# hv3layerSW.net
KiCad netlist of a schematic drawn in EAGLE
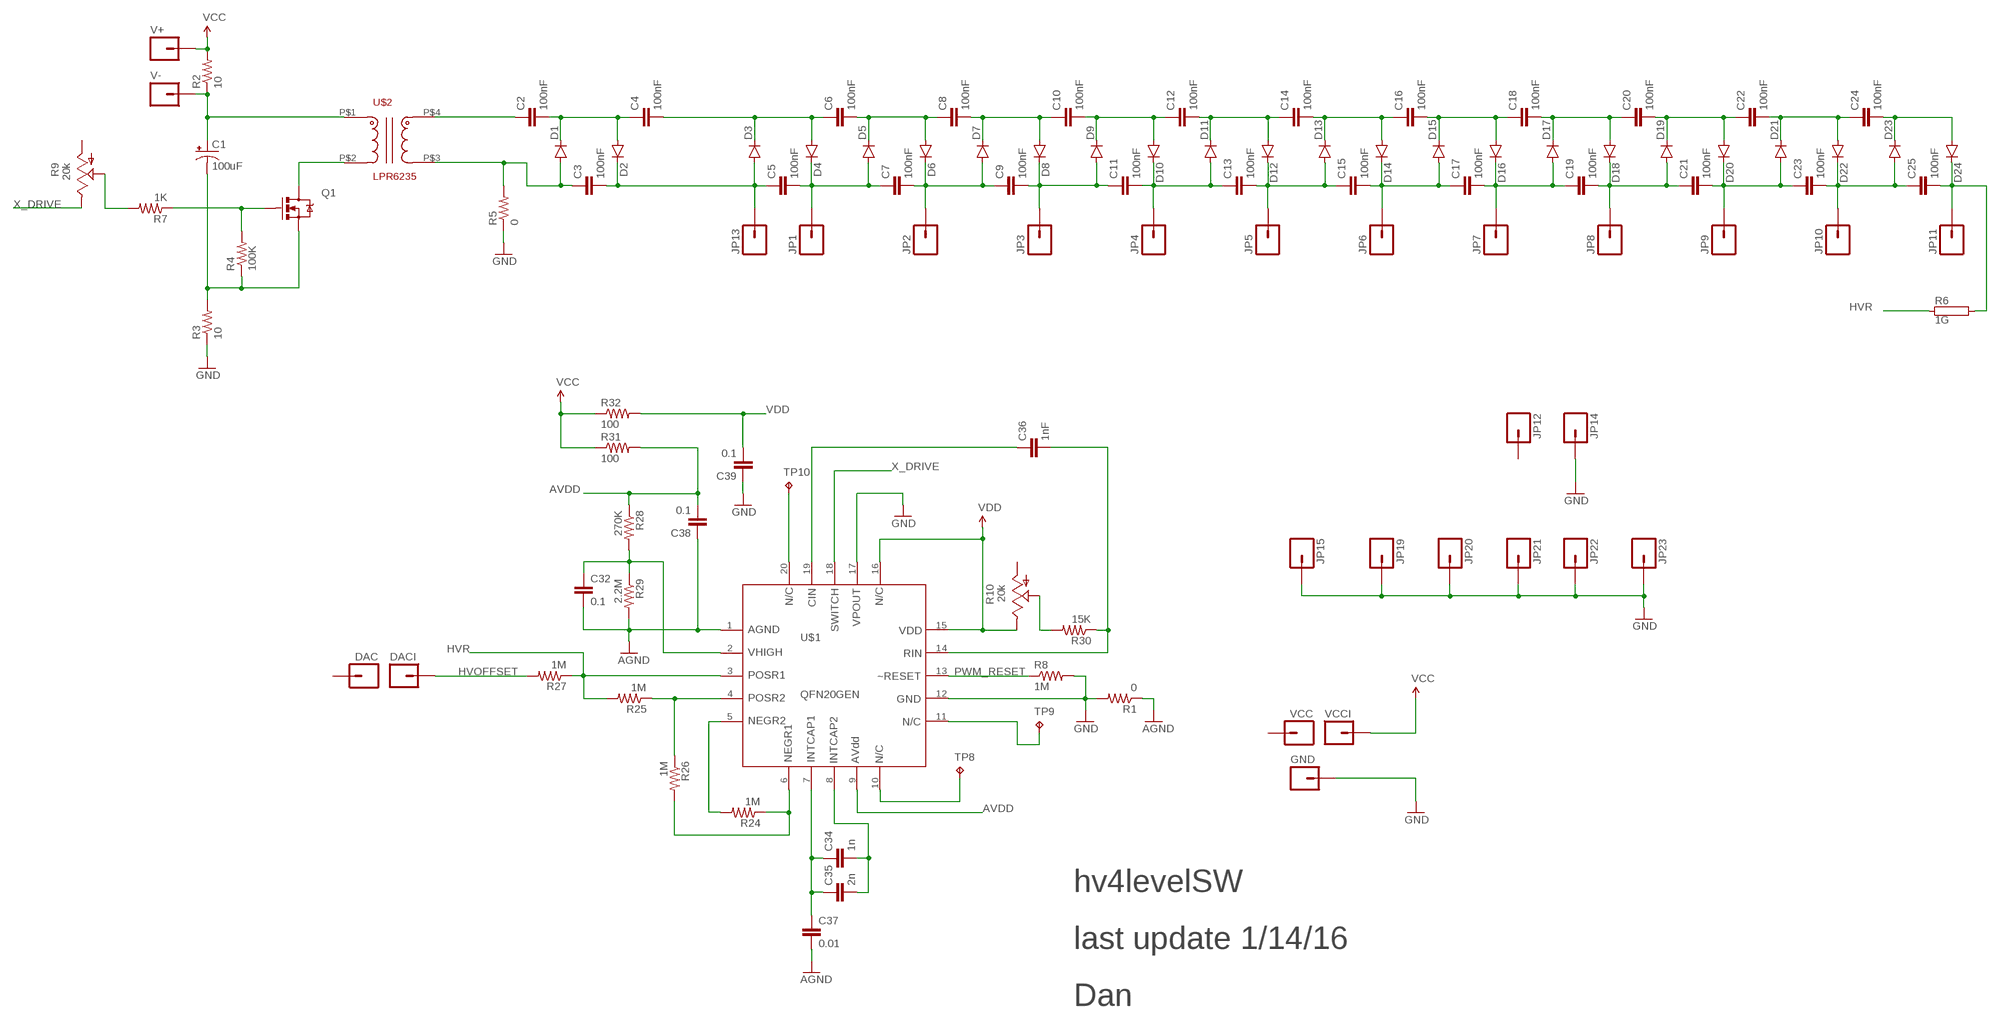
[diagram p0: schematic, sheet 1]

(export (version "E")
  (design (tool "Eeschema 10.0.6"))
  (components
    (comp (ref "C1")
      (value "100uF")
      (footprint "eagle-import:EIA6032")
      (libsource (lib "eagle-import") (part "CAP_POL6032"))
    )
    (comp (ref "C2")
      (value "100nF")
      (footprint "eagle-import:1210")
      (libsource (lib "eagle-import") (part "CAP1210"))
    )
    (comp (ref "C3")
      (value "100nF")
      (footprint "eagle-import:1210")
      (libsource (lib "eagle-import") (part "CAP1210"))
    )
    (comp (ref "C4")
      (value "100nF")
      (footprint "eagle-import:1210")
      (libsource (lib "eagle-import") (part "CAP1210"))
    )
    (comp (ref "C5")
      (value "100nF")
      (footprint "eagle-import:1210")
      (libsource (lib "eagle-import") (part "CAP1210"))
    )
    (comp (ref "C6")
      (value "100nF")
      (footprint "eagle-import:1210")
      (libsource (lib "eagle-import") (part "CAP1210"))
    )
    (comp (ref "C7")
      (value "100nF")
      (footprint "eagle-import:1210")
      (libsource (lib "eagle-import") (part "CAP1210"))
    )
    (comp (ref "C8")
      (value "100nF")
      (footprint "eagle-import:1210")
      (libsource (lib "eagle-import") (part "CAP1210"))
    )
    (comp (ref "C9")
      (value "100nF")
      (footprint "eagle-import:1210")
      (libsource (lib "eagle-import") (part "CAP1210"))
    )
    (comp (ref "C10")
      (value "100nF")
      (footprint "eagle-import:1210")
      (libsource (lib "eagle-import") (part "CAP1210"))
    )
    (comp (ref "C11")
      (value "100nF")
      (footprint "eagle-import:1210")
      (libsource (lib "eagle-import") (part "CAP1210"))
    )
    (comp (ref "C12")
      (value "100nF")
      (footprint "eagle-import:1210")
      (libsource (lib "eagle-import") (part "CAP1210"))
    )
    (comp (ref "C13")
      (value "100nF")
      (footprint "eagle-import:1210")
      (libsource (lib "eagle-import") (part "CAP1210"))
    )
    (comp (ref "C14")
      (value "100nF")
      (footprint "eagle-import:1210")
      (libsource (lib "eagle-import") (part "CAP1210"))
    )
    (comp (ref "C15")
      (value "100nF")
      (footprint "eagle-import:1210")
      (libsource (lib "eagle-import") (part "CAP1210"))
    )
    (comp (ref "C16")
      (value "100nF")
      (footprint "eagle-import:1210")
      (libsource (lib "eagle-import") (part "CAP1210"))
    )
    (comp (ref "C17")
      (value "100nF")
      (footprint "eagle-import:1210")
      (libsource (lib "eagle-import") (part "CAP1210"))
    )
    (comp (ref "C18")
      (value "100nF")
      (footprint "eagle-import:1210")
      (libsource (lib "eagle-import") (part "CAP1210"))
    )
    (comp (ref "C19")
      (value "100nF")
      (footprint "eagle-import:1210")
      (libsource (lib "eagle-import") (part "CAP1210"))
    )
    (comp (ref "C20")
      (value "100nF")
      (footprint "eagle-import:1210")
      (libsource (lib "eagle-import") (part "CAP1210"))
    )
    (comp (ref "C21")
      (value "100nF")
      (footprint "eagle-import:1210")
      (libsource (lib "eagle-import") (part "CAP1210"))
    )
    (comp (ref "C22")
      (value "100nF")
      (footprint "eagle-import:1210")
      (libsource (lib "eagle-import") (part "CAP1210"))
    )
    (comp (ref "C23")
      (value "100nF")
      (footprint "eagle-import:1210")
      (libsource (lib "eagle-import") (part "CAP1210"))
    )
    (comp (ref "C24")
      (value "100nF")
      (footprint "eagle-import:1210")
      (libsource (lib "eagle-import") (part "CAP1210"))
    )
    (comp (ref "C25")
      (value "100nF")
      (footprint "eagle-import:1210")
      (libsource (lib "eagle-import") (part "CAP1210"))
    )
    (comp (ref "C32")
      (value "0.1")
      (footprint "eagle-import:0805")
      (libsource (lib "eagle-import") (part "22UF-6.3V-20%(0805)"))
    )
    (comp (ref "C34")
      (value "1n")
      (footprint "eagle-import:0805")
      (libsource (lib "eagle-import") (part "22UF-6.3V-20%(0805)"))
    )
    (comp (ref "C35")
      (value "2n")
      (footprint "eagle-import:0805")
      (libsource (lib "eagle-import") (part "22UF-6.3V-20%(0805)"))
    )
    (comp (ref "C36")
      (value "1nF")
      (footprint "eagle-import:0805")
      (libsource (lib "eagle-import") (part "22UF-6.3V-20%(0805)"))
    )
    (comp (ref "C37")
      (value "0.01")
      (footprint "eagle-import:0805")
      (libsource (lib "eagle-import") (part "22UF-6.3V-20%(0805)"))
    )
    (comp (ref "C38")
      (value "0.1")
      (footprint "eagle-import:0805")
      (libsource (lib "eagle-import") (part "22UF-6.3V-20%(0805)"))
    )
    (comp (ref "C39")
      (value "0.1")
      (footprint "eagle-import:0805")
      (libsource (lib "eagle-import") (part "22UF-6.3V-20%(0805)"))
    )
    (comp (ref "D1")
      (value "DIODESOT23")
      (footprint "eagle-import:SOT23-3")
      (libsource (lib "eagle-import") (part "DIODESOT23"))
    )
    (comp (ref "D2")
      (value "DIODESOT23")
      (footprint "eagle-import:SOT23-3")
      (libsource (lib "eagle-import") (part "DIODESOT23"))
    )
    (comp (ref "D3")
      (value "DIODESOT23")
      (footprint "eagle-import:SOT23-3")
      (libsource (lib "eagle-import") (part "DIODESOT23"))
    )
    (comp (ref "D4")
      (value "DIODESOT23")
      (footprint "eagle-import:SOT23-3")
      (libsource (lib "eagle-import") (part "DIODESOT23"))
    )
    (comp (ref "D5")
      (value "DIODESOT23")
      (footprint "eagle-import:SOT23-3")
      (libsource (lib "eagle-import") (part "DIODESOT23"))
    )
    (comp (ref "D6")
      (value "DIODESOT23")
      (footprint "eagle-import:SOT23-3")
      (libsource (lib "eagle-import") (part "DIODESOT23"))
    )
    (comp (ref "D7")
      (value "DIODESOT23")
      (footprint "eagle-import:SOT23-3")
      (libsource (lib "eagle-import") (part "DIODESOT23"))
    )
    (comp (ref "D8")
      (value "DIODESOT23")
      (footprint "eagle-import:SOT23-3")
      (libsource (lib "eagle-import") (part "DIODESOT23"))
    )
    (comp (ref "D9")
      (value "DIODESOT23")
      (footprint "eagle-import:SOT23-3")
      (libsource (lib "eagle-import") (part "DIODESOT23"))
    )
    (comp (ref "D10")
      (value "DIODESOT23")
      (footprint "eagle-import:SOT23-3")
      (libsource (lib "eagle-import") (part "DIODESOT23"))
    )
    (comp (ref "D11")
      (value "DIODESOT23")
      (footprint "eagle-import:SOT23-3")
      (libsource (lib "eagle-import") (part "DIODESOT23"))
    )
    (comp (ref "D12")
      (value "DIODESOT23")
      (footprint "eagle-import:SOT23-3")
      (libsource (lib "eagle-import") (part "DIODESOT23"))
    )
    (comp (ref "D13")
      (value "DIODESOT23")
      (footprint "eagle-import:SOT23-3")
      (libsource (lib "eagle-import") (part "DIODESOT23"))
    )
    (comp (ref "D14")
      (value "DIODESOT23")
      (footprint "eagle-import:SOT23-3")
      (libsource (lib "eagle-import") (part "DIODESOT23"))
    )
    (comp (ref "D15")
      (value "DIODESOT23")
      (footprint "eagle-import:SOT23-3")
      (libsource (lib "eagle-import") (part "DIODESOT23"))
    )
    (comp (ref "D16")
      (value "DIODESOT23")
      (footprint "eagle-import:SOT23-3")
      (libsource (lib "eagle-import") (part "DIODESOT23"))
    )
    (comp (ref "D17")
      (value "DIODESOT23")
      (footprint "eagle-import:SOT23-3")
      (libsource (lib "eagle-import") (part "DIODESOT23"))
    )
    (comp (ref "D18")
      (value "DIODESOT23")
      (footprint "eagle-import:SOT23-3")
      (libsource (lib "eagle-import") (part "DIODESOT23"))
    )
    (comp (ref "D19")
      (value "DIODESOT23")
      (footprint "eagle-import:SOT23-3")
      (libsource (lib "eagle-import") (part "DIODESOT23"))
    )
    (comp (ref "D20")
      (value "DIODESOT23")
      (footprint "eagle-import:SOT23-3")
      (libsource (lib "eagle-import") (part "DIODESOT23"))
    )
    (comp (ref "D21")
      (value "DIODESOT23")
      (footprint "eagle-import:SOT23-3")
      (libsource (lib "eagle-import") (part "DIODESOT23"))
    )
    (comp (ref "D22")
      (value "DIODESOT23")
      (footprint "eagle-import:SOT23-3")
      (libsource (lib "eagle-import") (part "DIODESOT23"))
    )
    (comp (ref "D23")
      (value "DIODESOT23")
      (footprint "eagle-import:SOT23-3")
      (libsource (lib "eagle-import") (part "DIODESOT23"))
    )
    (comp (ref "D24")
      (value "DIODESOT23")
      (footprint "eagle-import:SOT23-3")
      (libsource (lib "eagle-import") (part "DIODESOT23"))
    )
    (comp (ref "DAC")
      (value "M01PTH")
      (footprint "eagle-import:1X01")
      (libsource (lib "eagle-import") (part "M01PTH"))
    )
    (comp (ref "DACI")
      (value "M01PTH")
      (footprint "eagle-import:1X01")
      (libsource (lib "eagle-import") (part "M01PTH"))
    )
    (comp (ref "GND")
      (value "M01PTH")
      (footprint "eagle-import:1X01")
      (libsource (lib "eagle-import") (part "M01PTH"))
    )
    (comp (ref "JP1")
      (value "M01PTH")
      (footprint "eagle-import:1X01")
      (libsource (lib "eagle-import") (part "M01PTH"))
    )
    (comp (ref "JP2")
      (value "M01PTH")
      (footprint "eagle-import:1X01")
      (libsource (lib "eagle-import") (part "M01PTH"))
    )
    (comp (ref "JP3")
      (value "M01PTH")
      (footprint "eagle-import:1X01")
      (libsource (lib "eagle-import") (part "M01PTH"))
    )
    (comp (ref "JP4")
      (value "M01PTH")
      (footprint "eagle-import:1X01")
      (libsource (lib "eagle-import") (part "M01PTH"))
    )
    (comp (ref "JP5")
      (value "M01PTH")
      (footprint "eagle-import:1X01")
      (libsource (lib "eagle-import") (part "M01PTH"))
    )
    (comp (ref "JP6")
      (value "M01PTH")
      (footprint "eagle-import:1X01")
      (libsource (lib "eagle-import") (part "M01PTH"))
    )
    (comp (ref "JP7")
      (value "M01PTH")
      (footprint "eagle-import:1X01")
      (libsource (lib "eagle-import") (part "M01PTH"))
    )
    (comp (ref "JP8")
      (value "M01PTH")
      (footprint "eagle-import:1X01")
      (libsource (lib "eagle-import") (part "M01PTH"))
    )
    (comp (ref "JP9")
      (value "M01PTH")
      (footprint "eagle-import:1X01")
      (libsource (lib "eagle-import") (part "M01PTH"))
    )
    (comp (ref "JP10")
      (value "M01PTH")
      (footprint "eagle-import:1X01")
      (libsource (lib "eagle-import") (part "M01PTH"))
    )
    (comp (ref "JP11")
      (value "M01PTH")
      (footprint "eagle-import:1X01")
      (libsource (lib "eagle-import") (part "M01PTH"))
    )
    (comp (ref "JP12")
      (value "M01PTH")
      (footprint "eagle-import:1X01")
      (libsource (lib "eagle-import") (part "M01PTH"))
    )
    (comp (ref "JP13")
      (value "M01PTH")
      (footprint "eagle-import:1X01")
      (libsource (lib "eagle-import") (part "M01PTH"))
    )
    (comp (ref "JP14")
      (value "M01PTH")
      (footprint "eagle-import:1X01")
      (libsource (lib "eagle-import") (part "M01PTH"))
    )
    (comp (ref "JP15")
      (value "M01PTH")
      (footprint "eagle-import:1X01")
      (libsource (lib "eagle-import") (part "M01PTH"))
    )
    (comp (ref "JP19")
      (value "M01PTH")
      (footprint "eagle-import:1X01")
      (libsource (lib "eagle-import") (part "M01PTH"))
    )
    (comp (ref "JP20")
      (value "M01PTH")
      (footprint "eagle-import:1X01")
      (libsource (lib "eagle-import") (part "M01PTH"))
    )
    (comp (ref "JP21")
      (value "M01PTH")
      (footprint "eagle-import:1X01")
      (libsource (lib "eagle-import") (part "M01PTH"))
    )
    (comp (ref "JP22")
      (value "M01PTH")
      (footprint "eagle-import:1X01")
      (libsource (lib "eagle-import") (part "M01PTH"))
    )
    (comp (ref "JP23")
      (value "M01PTH")
      (footprint "eagle-import:1X01")
      (libsource (lib "eagle-import") (part "M01PTH"))
    )
    (comp (ref "Q1")
      (value "MOSFET-NCHANNELAO3404A")
      (footprint "eagle-import:SOT23-3")
      (libsource (lib "eagle-import") (part "MOSFET-NCHANNELAO3404A"))
    )
    (comp (ref "R1")
      (value "0")
      (footprint "eagle-import:0805")
      (libsource (lib "eagle-import") (part "RESISTOR0805-RES"))
    )
    (comp (ref "R2")
      (value "10")
      (footprint "eagle-import:R2512")
      (libsource (lib "eagle-import") (part "SparkFun-Resistors_RESISTOR2512"))
    )
    (comp (ref "R3")
      (value "10")
      (footprint "eagle-import:R2512")
      (libsource (lib "eagle-import") (part "SparkFun-Resistors_RESISTOR2512"))
    )
    (comp (ref "R4")
      (value "100K")
      (footprint "eagle-import:0805")
      (libsource (lib "eagle-import") (part "RESISTOR0805-RES"))
    )
    (comp (ref "R5")
      (value "0")
      (footprint "eagle-import:0805")
      (libsource (lib "eagle-import") (part "RESISTOR0805-RES"))
    )
    (comp (ref "R6")
      (value "1G")
      (footprint "eagle-import:CA4090")
      (libsource (lib "eagle-import") (part "RCA4090"))
    )
    (comp (ref "R7")
      (value "1K")
      (footprint "eagle-import:0805")
      (libsource (lib "eagle-import") (part "RESISTOR0805-RES"))
    )
    (comp (ref "R8")
      (value "1M")
      (footprint "eagle-import:0805")
      (libsource (lib "eagle-import") (part "RESISTOR0805-RES"))
    )
    (comp (ref "R9")
      (value "20k")
      (footprint "eagle-import:3223J")
      (libsource (lib "eagle-import") (part "TRIM_US-3223J"))
    )
    (comp (ref "R10")
      (value "20k")
      (footprint "eagle-import:3223J")
      (libsource (lib "eagle-import") (part "TRIM_US-3223J"))
    )
    (comp (ref "R24")
      (value "1M")
      (footprint "eagle-import:0805")
      (libsource (lib "eagle-import") (part "RESISTOR0805-RES"))
    )
    (comp (ref "R25")
      (value "1M")
      (footprint "eagle-import:0805")
      (libsource (lib "eagle-import") (part "RESISTOR0805-RES"))
    )
    (comp (ref "R26")
      (value "1M")
      (footprint "eagle-import:0805")
      (libsource (lib "eagle-import") (part "RESISTOR0805-RES"))
    )
    (comp (ref "R27")
      (value "1M")
      (footprint "eagle-import:0805")
      (libsource (lib "eagle-import") (part "RESISTOR0805-RES"))
    )
    (comp (ref "R28")
      (value "270K")
      (footprint "eagle-import:0805")
      (libsource (lib "eagle-import") (part "RESISTOR0805-RES"))
    )
    (comp (ref "R29")
      (value "2.2M")
      (footprint "eagle-import:0805")
      (libsource (lib "eagle-import") (part "RESISTOR0805-RES"))
    )
    (comp (ref "R30")
      (value "15K")
      (footprint "eagle-import:0805")
      (libsource (lib "eagle-import") (part "RESISTOR0805-RES"))
    )
    (comp (ref "R31")
      (value "100")
      (footprint "eagle-import:0805")
      (libsource (lib "eagle-import") (part "RESISTOR0805-RES"))
    )
    (comp (ref "R32")
      (value "100")
      (footprint "eagle-import:0805")
      (libsource (lib "eagle-import") (part "RESISTOR0805-RES"))
    )
    (comp (ref "TP8")
      (value "TPTP10R")
      (footprint "eagle-import:TP10R")
      (libsource (lib "eagle-import") (part "TPTP10R"))
    )
    (comp (ref "TP9")
      (value "TPTP10R")
      (footprint "eagle-import:TP10R")
      (libsource (lib "eagle-import") (part "TPTP10R"))
    )
    (comp (ref "TP10")
      (value "TPTP10R")
      (footprint "eagle-import:TP10R")
      (libsource (lib "eagle-import") (part "TPTP10R"))
    )
    (comp (ref "U$1")
      (value "QFN20GEN")
      (footprint "eagle-import:QFN20")
      (libsource (lib "eagle-import") (part "QFN20GEN"))
    )
    (comp (ref "U$2")
      (value "LPR6235")
      (footprint "eagle-import:LPR6235")
      (libsource (lib "eagle-import") (part "LPR6235"))
    )
    (comp (ref "V+")
      (value "M01PTH")
      (footprint "eagle-import:1X01")
      (libsource (lib "eagle-import") (part "M01PTH"))
    )
    (comp (ref "V-")
      (value "M01PTH")
      (footprint "eagle-import:1X01")
      (libsource (lib "eagle-import") (part "M01PTH"))
    )
    (comp (ref "VCC")
      (value "M01PTH")
      (footprint "eagle-import:1X01")
      (libsource (lib "eagle-import") (part "M01PTH"))
    )
    (comp (ref "VCCI")
      (value "M01PTH")
      (footprint "eagle-import:1X01")
      (libsource (lib "eagle-import") (part "M01PTH"))
    )
  )
  (nets
    (net (code "1") (name "/AVDD") (class "Default")
      (node (ref "C38") (pin "2") (pinfunction "2_2") (pintype "passive"))
      (node (ref "R28") (pin "1") (pinfunction "1_1") (pintype "passive"))
      (node (ref "R31") (pin "2") (pinfunction "2_2") (pintype "passive"))
      (node (ref "U$1") (pin "9") (pinfunction "P$9_9") (pintype "bidirectional"))
    )
    (net (code "2") (name "/HVOFFSET") (class "Default")
      (node (ref "DACI") (pin "1") (pinfunction "1_1") (pintype "passive"))
      (node (ref "R27") (pin "2") (pinfunction "2_2") (pintype "passive"))
    )
    (net (code "3") (name "/HVR") (class "Default")
      (node (ref "R25") (pin "2") (pinfunction "2_2") (pintype "passive"))
      (node (ref "R27") (pin "1") (pinfunction "1_1") (pintype "passive"))
      (node (ref "R6") (pin "1") (pinfunction "1_1") (pintype "passive"))
      (node (ref "U$1") (pin "3") (pinfunction "P$3_3") (pintype "bidirectional"))
    )
    (net (code "4") (name "/PWM_RESET") (class "Default")
      (node (ref "R8") (pin "1") (pinfunction "1_1") (pintype "passive"))
      (node (ref "U$1") (pin "13") (pinfunction "P$13_13") (pintype "bidirectional"))
    )
    (net (code "5") (name "/X_DRIVE") (class "Default")
      (node (ref "R9") (pin "3") (pinfunction "E_3") (pintype "passive"))
      (node (ref "U$1") (pin "18") (pinfunction "P$18_18") (pintype "bidirectional"))
    )
    (net (code "6") (name "AGND") (class "Default")
      (node (ref "C32") (pin "2") (pinfunction "2_2") (pintype "passive"))
      (node (ref "C37") (pin "2") (pinfunction "2_2") (pintype "passive"))
      (node (ref "C38") (pin "1") (pinfunction "1_1") (pintype "passive"))
      (node (ref "R1") (pin "1") (pinfunction "1_1") (pintype "passive"))
      (node (ref "R29") (pin "2") (pinfunction "2_2") (pintype "passive"))
      (node (ref "U$1") (pin "1") (pinfunction "P$1_1") (pintype "bidirectional"))
    )
    (net (code "7") (name "GND") (class "Default")
      (node (ref "C39") (pin "1") (pinfunction "1_1") (pintype "passive"))
      (node (ref "GND") (pin "1") (pinfunction "1_1") (pintype "passive"))
      (node (ref "JP14") (pin "1") (pinfunction "1_1") (pintype "passive"))
      (node (ref "JP15") (pin "1") (pinfunction "1_1") (pintype "passive"))
      (node (ref "JP19") (pin "1") (pinfunction "1_1") (pintype "passive"))
      (node (ref "JP20") (pin "1") (pinfunction "1_1") (pintype "passive"))
      (node (ref "JP21") (pin "1") (pinfunction "1_1") (pintype "passive"))
      (node (ref "JP22") (pin "1") (pinfunction "1_1") (pintype "passive"))
      (node (ref "JP23") (pin "1") (pinfunction "1_1") (pintype "passive"))
      (node (ref "R1") (pin "2") (pinfunction "2_2") (pintype "passive"))
      (node (ref "R3") (pin "1") (pinfunction "1_1") (pintype "passive"))
      (node (ref "R5") (pin "1") (pinfunction "1_1") (pintype "passive"))
      (node (ref "R8") (pin "2") (pinfunction "2_2") (pintype "passive"))
      (node (ref "U$1") (pin "12") (pinfunction "P$12_12") (pintype "bidirectional"))
      (node (ref "U$1") (pin "17") (pinfunction "P$17_17") (pintype "bidirectional"))
    )
    (net (code "8") (name "Net-(C1-+)") (class "Default")
      (node (ref "C1") (pin "P$1") (pinfunction "+_P$1") (pintype "passive"))
      (node (ref "R2") (pin "1") (pinfunction "1_1") (pintype "passive"))
      (node (ref "U$2") (pin "P$1") (pinfunction "1_P$1") (pintype "passive"))
      (node (ref "V-") (pin "1") (pinfunction "1_1") (pintype "passive"))
    )
    (net (code "9") (name "Net-(C1--)") (class "Default")
      (node (ref "C1") (pin "P$2") (pinfunction "-_P$2") (pintype "passive"))
      (node (ref "Q1") (pin "2") (pinfunction "S_2") (pintype "passive"))
      (node (ref "R3") (pin "2") (pinfunction "2_2") (pintype "passive"))
      (node (ref "R4") (pin "1") (pinfunction "1_1") (pintype "passive"))
    )
    (net (code "10") (name "Net-(D1-A)") (class "Default")
      (node (ref "C3") (pin "1") (pinfunction "1_1") (pintype "passive"))
      (node (ref "D1") (pin "1") (pinfunction "A_1") (pintype "passive"))
      (node (ref "R5") (pin "2") (pinfunction "2_2") (pintype "passive"))
      (node (ref "U$2") (pin "P$3") (pinfunction "5_P$3") (pintype "passive"))
    )
    (net (code "11") (name "Net-(D1-C)") (class "Default")
      (node (ref "C2") (pin "2") (pinfunction "2_2") (pintype "passive"))
      (node (ref "C4") (pin "1") (pinfunction "1_1") (pintype "passive"))
      (node (ref "D1") (pin "3") (pinfunction "C_3") (pintype "passive"))
      (node (ref "D2") (pin "1") (pinfunction "A_1") (pintype "passive"))
    )
    (net (code "12") (name "Net-(D2-C)") (class "Default")
      (node (ref "C3") (pin "2") (pinfunction "2_2") (pintype "passive"))
      (node (ref "C5") (pin "1") (pinfunction "1_1") (pintype "passive"))
      (node (ref "D2") (pin "3") (pinfunction "C_3") (pintype "passive"))
      (node (ref "D3") (pin "1") (pinfunction "A_1") (pintype "passive"))
      (node (ref "JP13") (pin "1") (pinfunction "1_1") (pintype "passive"))
    )
    (net (code "13") (name "Net-(D3-C)") (class "Default")
      (node (ref "C4") (pin "2") (pinfunction "2_2") (pintype "passive"))
      (node (ref "C6") (pin "1") (pinfunction "1_1") (pintype "passive"))
      (node (ref "D3") (pin "3") (pinfunction "C_3") (pintype "passive"))
      (node (ref "D4") (pin "1") (pinfunction "A_1") (pintype "passive"))
    )
    (net (code "14") (name "Net-(D4-C)") (class "Default")
      (node (ref "C5") (pin "2") (pinfunction "2_2") (pintype "passive"))
      (node (ref "C7") (pin "1") (pinfunction "1_1") (pintype "passive"))
      (node (ref "D4") (pin "3") (pinfunction "C_3") (pintype "passive"))
      (node (ref "D5") (pin "1") (pinfunction "A_1") (pintype "passive"))
      (node (ref "JP1") (pin "1") (pinfunction "1_1") (pintype "passive"))
    )
    (net (code "15") (name "Net-(D5-C)") (class "Default")
      (node (ref "C6") (pin "2") (pinfunction "2_2") (pintype "passive"))
      (node (ref "C8") (pin "1") (pinfunction "1_1") (pintype "passive"))
      (node (ref "D5") (pin "3") (pinfunction "C_3") (pintype "passive"))
      (node (ref "D6") (pin "1") (pinfunction "A_1") (pintype "passive"))
    )
    (net (code "16") (name "Net-(D6-C)") (class "Default")
      (node (ref "C7") (pin "2") (pinfunction "2_2") (pintype "passive"))
      (node (ref "C9") (pin "1") (pinfunction "1_1") (pintype "passive"))
      (node (ref "D6") (pin "3") (pinfunction "C_3") (pintype "passive"))
      (node (ref "D7") (pin "1") (pinfunction "A_1") (pintype "passive"))
      (node (ref "JP2") (pin "1") (pinfunction "1_1") (pintype "passive"))
    )
    (net (code "17") (name "Net-(D7-C)") (class "Default")
      (node (ref "C10") (pin "1") (pinfunction "1_1") (pintype "passive"))
      (node (ref "C8") (pin "2") (pinfunction "2_2") (pintype "passive"))
      (node (ref "D7") (pin "3") (pinfunction "C_3") (pintype "passive"))
      (node (ref "D8") (pin "1") (pinfunction "A_1") (pintype "passive"))
    )
    (net (code "18") (name "Net-(D8-C)") (class "Default")
      (node (ref "C11") (pin "1") (pinfunction "1_1") (pintype "passive"))
      (node (ref "C9") (pin "2") (pinfunction "2_2") (pintype "passive"))
      (node (ref "D8") (pin "3") (pinfunction "C_3") (pintype "passive"))
      (node (ref "D9") (pin "1") (pinfunction "A_1") (pintype "passive"))
      (node (ref "JP3") (pin "1") (pinfunction "1_1") (pintype "passive"))
    )
    (net (code "19") (name "Net-(D10-A)") (class "Default")
      (node (ref "C10") (pin "2") (pinfunction "2_2") (pintype "passive"))
      (node (ref "C12") (pin "1") (pinfunction "1_1") (pintype "passive"))
      (node (ref "D10") (pin "1") (pinfunction "A_1") (pintype "passive"))
      (node (ref "D9") (pin "3") (pinfunction "C_3") (pintype "passive"))
    )
    (net (code "20") (name "Net-(D10-C)") (class "Default")
      (node (ref "C11") (pin "2") (pinfunction "2_2") (pintype "passive"))
      (node (ref "C13") (pin "1") (pinfunction "1_1") (pintype "passive"))
      (node (ref "D10") (pin "3") (pinfunction "C_3") (pintype "passive"))
      (node (ref "D11") (pin "1") (pinfunction "A_1") (pintype "passive"))
      (node (ref "JP4") (pin "1") (pinfunction "1_1") (pintype "passive"))
    )
    (net (code "21") (name "Net-(D11-C)") (class "Default")
      (node (ref "C12") (pin "2") (pinfunction "2_2") (pintype "passive"))
      (node (ref "C14") (pin "1") (pinfunction "1_1") (pintype "passive"))
      (node (ref "D11") (pin "3") (pinfunction "C_3") (pintype "passive"))
      (node (ref "D12") (pin "1") (pinfunction "A_1") (pintype "passive"))
    )
    (net (code "22") (name "Net-(D12-C)") (class "Default")
      (node (ref "C13") (pin "2") (pinfunction "2_2") (pintype "passive"))
      (node (ref "C15") (pin "1") (pinfunction "1_1") (pintype "passive"))
      (node (ref "D12") (pin "3") (pinfunction "C_3") (pintype "passive"))
      (node (ref "D13") (pin "1") (pinfunction "A_1") (pintype "passive"))
      (node (ref "JP5") (pin "1") (pinfunction "1_1") (pintype "passive"))
    )
    (net (code "23") (name "Net-(D13-C)") (class "Default")
      (node (ref "C14") (pin "2") (pinfunction "2_2") (pintype "passive"))
      (node (ref "C16") (pin "1") (pinfunction "1_1") (pintype "passive"))
      (node (ref "D13") (pin "3") (pinfunction "C_3") (pintype "passive"))
      (node (ref "D14") (pin "1") (pinfunction "A_1") (pintype "passive"))
    )
    (net (code "24") (name "Net-(D14-C)") (class "Default")
      (node (ref "C15") (pin "2") (pinfunction "2_2") (pintype "passive"))
      (node (ref "C17") (pin "1") (pinfunction "1_1") (pintype "passive"))
      (node (ref "D14") (pin "3") (pinfunction "C_3") (pintype "passive"))
      (node (ref "D15") (pin "1") (pinfunction "A_1") (pintype "passive"))
      (node (ref "JP6") (pin "1") (pinfunction "1_1") (pintype "passive"))
    )
    (net (code "25") (name "Net-(D15-C)") (class "Default")
      (node (ref "C16") (pin "2") (pinfunction "2_2") (pintype "passive"))
      (node (ref "C18") (pin "1") (pinfunction "1_1") (pintype "passive"))
      (node (ref "D15") (pin "3") (pinfunction "C_3") (pintype "passive"))
      (node (ref "D16") (pin "1") (pinfunction "A_1") (pintype "passive"))
    )
    (net (code "26") (name "Net-(D16-C)") (class "Default")
      (node (ref "C17") (pin "2") (pinfunction "2_2") (pintype "passive"))
      (node (ref "C19") (pin "1") (pinfunction "1_1") (pintype "passive"))
      (node (ref "D16") (pin "3") (pinfunction "C_3") (pintype "passive"))
      (node (ref "D17") (pin "1") (pinfunction "A_1") (pintype "passive"))
      (node (ref "JP7") (pin "1") (pinfunction "1_1") (pintype "passive"))
    )
    (net (code "27") (name "Net-(D17-C)") (class "Default")
      (node (ref "C18") (pin "2") (pinfunction "2_2") (pintype "passive"))
      (node (ref "C20") (pin "1") (pinfunction "1_1") (pintype "passive"))
      (node (ref "D17") (pin "3") (pinfunction "C_3") (pintype "passive"))
      (node (ref "D18") (pin "1") (pinfunction "A_1") (pintype "passive"))
    )
    (net (code "28") (name "Net-(D18-C)") (class "Default")
      (node (ref "C19") (pin "2") (pinfunction "2_2") (pintype "passive"))
      (node (ref "C21") (pin "1") (pinfunction "1_1") (pintype "passive"))
      (node (ref "D18") (pin "3") (pinfunction "C_3") (pintype "passive"))
      (node (ref "D19") (pin "1") (pinfunction "A_1") (pintype "passive"))
      (node (ref "JP8") (pin "1") (pinfunction "1_1") (pintype "passive"))
    )
    (net (code "29") (name "Net-(D19-C)") (class "Default")
      (node (ref "C20") (pin "2") (pinfunction "2_2") (pintype "passive"))
      (node (ref "C22") (pin "1") (pinfunction "1_1") (pintype "passive"))
      (node (ref "D19") (pin "3") (pinfunction "C_3") (pintype "passive"))
      (node (ref "D20") (pin "1") (pinfunction "A_1") (pintype "passive"))
    )
    (net (code "30") (name "Net-(D20-C)") (class "Default")
      (node (ref "C21") (pin "2") (pinfunction "2_2") (pintype "passive"))
      (node (ref "C23") (pin "1") (pinfunction "1_1") (pintype "passive"))
      (node (ref "D20") (pin "3") (pinfunction "C_3") (pintype "passive"))
      (node (ref "D21") (pin "1") (pinfunction "A_1") (pintype "passive"))
      (node (ref "JP9") (pin "1") (pinfunction "1_1") (pintype "passive"))
    )
    (net (code "31") (name "Net-(D21-C)") (class "Default")
      (node (ref "C22") (pin "2") (pinfunction "2_2") (pintype "passive"))
      (node (ref "C24") (pin "1") (pinfunction "1_1") (pintype "passive"))
      (node (ref "D21") (pin "3") (pinfunction "C_3") (pintype "passive"))
      (node (ref "D22") (pin "1") (pinfunction "A_1") (pintype "passive"))
    )
    (net (code "32") (name "Net-(D22-C)") (class "Default")
      (node (ref "C23") (pin "2") (pinfunction "2_2") (pintype "passive"))
      (node (ref "C25") (pin "1") (pinfunction "1_1") (pintype "passive"))
      (node (ref "D22") (pin "3") (pinfunction "C_3") (pintype "passive"))
      (node (ref "D23") (pin "1") (pinfunction "A_1") (pintype "passive"))
      (node (ref "JP10") (pin "1") (pinfunction "1_1") (pintype "passive"))
    )
    (net (code "33") (name "Net-(D23-C)") (class "Default")
      (node (ref "C24") (pin "2") (pinfunction "2_2") (pintype "passive"))
      (node (ref "D23") (pin "3") (pinfunction "C_3") (pintype "passive"))
      (node (ref "D24") (pin "1") (pinfunction "A_1") (pintype "passive"))
    )
    (net (code "34") (name "Net-(D24-C)") (class "Default")
      (node (ref "C25") (pin "2") (pinfunction "2_2") (pintype "passive"))
      (node (ref "D24") (pin "3") (pinfunction "C_3") (pintype "passive"))
      (node (ref "JP11") (pin "1") (pinfunction "1_1") (pintype "passive"))
      (node (ref "R6") (pin "2") (pinfunction "2_2") (pintype "passive"))
    )
    (net (code "35") (name "Net-(Q1-D)") (class "Default")
      (node (ref "Q1") (pin "3") (pinfunction "D_3") (pintype "passive"))
      (node (ref "U$2") (pin "P$2") (pinfunction "2_P$2") (pintype "passive"))
    )
    (net (code "36") (name "Net-(Q1-G)") (class "Default")
      (node (ref "Q1") (pin "1") (pinfunction "G_1") (pintype "passive"))
      (node (ref "R4") (pin "2") (pinfunction "2_2") (pintype "passive"))
      (node (ref "R7") (pin "1") (pinfunction "1_1") (pintype "passive"))
    )
    (net (code "37") (name "Net-(R9-S)") (class "Default")
      (node (ref "R7") (pin "2") (pinfunction "2_2") (pintype "passive"))
      (node (ref "R9") (pin "2") (pinfunction "S_2") (pintype "passive"))
    )
    (net (code "38") (name "Net-(R10-S)") (class "Default")
      (node (ref "R10") (pin "2") (pinfunction "S_2") (pintype "passive"))
      (node (ref "R30") (pin "2") (pinfunction "2_2") (pintype "passive"))
    )
    (net (code "39") (name "Net-(U$1-P$2)") (class "Default")
      (node (ref "C32") (pin "1") (pinfunction "1_1") (pintype "passive"))
      (node (ref "R28") (pin "2") (pinfunction "2_2") (pintype "passive"))
      (node (ref "R29") (pin "1") (pinfunction "1_1") (pintype "passive"))
      (node (ref "U$1") (pin "2") (pinfunction "P$2_2") (pintype "bidirectional"))
    )
    (net (code "40") (name "Net-(U$1-P$4)") (class "Default")
      (node (ref "R25") (pin "1") (pinfunction "1_1") (pintype "passive"))
      (node (ref "R26") (pin "1") (pinfunction "1_1") (pintype "passive"))
      (node (ref "U$1") (pin "4") (pinfunction "P$4_4") (pintype "bidirectional"))
    )
    (net (code "41") (name "Net-(U$1-P$5)") (class "Default")
      (node (ref "R24") (pin "2") (pinfunction "2_2") (pintype "passive"))
      (node (ref "U$1") (pin "5") (pinfunction "P$5_5") (pintype "bidirectional"))
    )
    (net (code "42") (name "Net-(U$1-P$6)") (class "Default")
      (node (ref "R24") (pin "1") (pinfunction "1_1") (pintype "passive"))
      (node (ref "R26") (pin "2") (pinfunction "2_2") (pintype "passive"))
      (node (ref "U$1") (pin "6") (pinfunction "P$6_6") (pintype "bidirectional"))
    )
    (net (code "43") (name "Net-(U$1-P$7)") (class "Default")
      (node (ref "C34") (pin "1") (pinfunction "1_1") (pintype "passive"))
      (node (ref "C35") (pin "1") (pinfunction "1_1") (pintype "passive"))
      (node (ref "C37") (pin "1") (pinfunction "1_1") (pintype "passive"))
      (node (ref "U$1") (pin "7") (pinfunction "P$7_7") (pintype "bidirectional"))
    )
    (net (code "44") (name "Net-(U$1-P$8)") (class "Default")
      (node (ref "C34") (pin "2") (pinfunction "2_2") (pintype "passive"))
      (node (ref "C35") (pin "2") (pinfunction "2_2") (pintype "passive"))
      (node (ref "U$1") (pin "8") (pinfunction "P$8_8") (pintype "bidirectional"))
    )
    (net (code "45") (name "Net-(U$1-P$10)") (class "Default")
      (node (ref "TP8") (pin "TP") (pinfunction "TP_TP") (pintype "input"))
      (node (ref "U$1") (pin "10") (pinfunction "P$10_10") (pintype "bidirectional"))
    )
    (net (code "46") (name "Net-(U$1-P$11)") (class "Default")
      (node (ref "TP9") (pin "TP") (pinfunction "TP_TP") (pintype "input"))
      (node (ref "U$1") (pin "11") (pinfunction "P$11_11") (pintype "bidirectional"))
    )
    (net (code "47") (name "Net-(U$1-P$14)") (class "Default")
      (node (ref "C36") (pin "2") (pinfunction "2_2") (pintype "passive"))
      (node (ref "R30") (pin "1") (pinfunction "1_1") (pintype "passive"))
      (node (ref "U$1") (pin "14") (pinfunction "P$14_14") (pintype "bidirectional"))
    )
    (net (code "48") (name "Net-(U$1-P$19)") (class "Default")
      (node (ref "C36") (pin "1") (pinfunction "1_1") (pintype "passive"))
      (node (ref "U$1") (pin "19") (pinfunction "P$19_19") (pintype "bidirectional"))
    )
    (net (code "49") (name "Net-(U$1-P$20)") (class "Default")
      (node (ref "TP10") (pin "TP") (pinfunction "TP_TP") (pintype "input"))
      (node (ref "U$1") (pin "20") (pinfunction "P$20_20") (pintype "bidirectional"))
    )
    (net (code "50") (name "Net-(U$2-4)") (class "Default")
      (node (ref "C2") (pin "1") (pinfunction "1_1") (pintype "passive"))
      (node (ref "U$2") (pin "P$4") (pinfunction "4_P$4") (pintype "passive"))
    )
    (net (code "51") (name "VCC") (class "Default")
      (node (ref "R2") (pin "2") (pinfunction "2_2") (pintype "passive"))
      (node (ref "R31") (pin "1") (pinfunction "1_1") (pintype "passive"))
      (node (ref "R32") (pin "1") (pinfunction "1_1") (pintype "passive"))
      (node (ref "V+") (pin "1") (pinfunction "1_1") (pintype "passive"))
      (node (ref "VCCI") (pin "1") (pinfunction "1_1") (pintype "passive"))
    )
    (net (code "52") (name "VDD") (class "Default")
      (node (ref "C39") (pin "2") (pinfunction "2_2") (pintype "passive"))
      (node (ref "R10") (pin "3") (pinfunction "E_3") (pintype "passive"))
      (node (ref "R32") (pin "2") (pinfunction "2_2") (pintype "passive"))
      (node (ref "U$1") (pin "15") (pinfunction "P$15_15") (pintype "bidirectional"))
      (node (ref "U$1") (pin "16") (pinfunction "P$16_16") (pintype "bidirectional"))
    )
    (net (code "53") (name "unconnected-(DAC-Pad1)") (class "Default")
      (node (ref "DAC") (pin "1") (pinfunction "1_1") (pintype "passive"))
    )
    (net (code "54") (name "unconnected-(JP12-Pad1)") (class "Default")
      (node (ref "JP12") (pin "1") (pinfunction "1_1") (pintype "passive"))
    )
    (net (code "55") (name "unconnected-(R9-A-Pad1)") (class "Default")
      (node (ref "R9") (pin "1") (pinfunction "A_1") (pintype "passive"))
    )
    (net (code "56") (name "unconnected-(R10-A-Pad1)") (class "Default")
      (node (ref "R10") (pin "1") (pinfunction "A_1") (pintype "passive"))
    )
    (net (code "57") (name "unconnected-(VCC-Pad1)") (class "Default")
      (node (ref "VCC") (pin "1") (pinfunction "1_1") (pintype "passive"))
    )
  )
)
